# SKC_PSU.net
KiCad netlist of a schematic drawn in Altium Designer
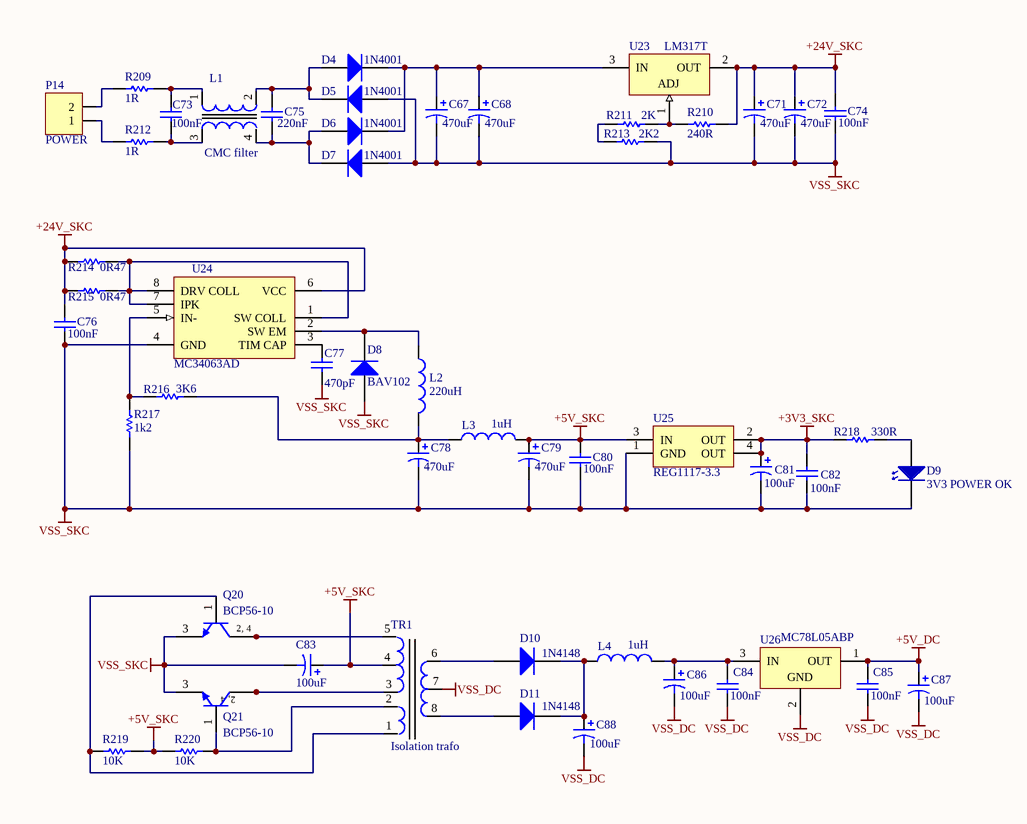
[diagram p0: SKC_PSU.SchDoc]

(export (version "E")
  (design (tool "Eeschema 10.0.6"))
  (components
    (comp (ref "C67")
      (value "470uF")
      (footprint "CAPPR5-10X16")
      (description "Aluminum Electrolytic Capacitor, Radial Style with Long Leads: 470uF, 35V")
      (fields (field (name "PUBLISHER") "Altium Limited"))
      (libsource (lib "Vishay Roederstein Electrolytic Radial-Lead Capacitor") (part "EKA00DD347F00"))
    )
    (comp (ref "C68")
      (value "470uF")
      (footprint "CAPPR5-10X16")
      (description "Aluminum Electrolytic Capacitor, Radial Style with Long Leads: 470uF, 35V")
      (fields (field (name "PUBLISHER") "Altium Limited"))
      (libsource (lib "Vishay Roederstein Electrolytic Radial-Lead Capacitor") (part "EKA00DD347F00"))
    )
    (comp (ref "C71")
      (value "470uF")
      (footprint "CAPPR5-10X16")
      (description "Aluminum Electrolytic Capacitor, Radial Style with Long Leads: 470uF, 35V")
      (fields (field (name "PUBLISHER") "Altium Limited"))
      (libsource (lib "Vishay Roederstein Electrolytic Radial-Lead Capacitor") (part "EKA00DD347F00"))
    )
    (comp (ref "C72")
      (value "470uF")
      (footprint "CAPPR5-10X16")
      (description "Aluminum Electrolytic Capacitor, Radial Style with Long Leads: 470uF, 35V")
      (fields (field (name "PUBLISHER") "Altium Limited"))
      (libsource (lib "Vishay Roederstein Electrolytic Radial-Lead Capacitor") (part "EKA00DD347F00"))
    )
    (comp (ref "C73")
      (value "100nF")
      (footprint "VP60-3.6")
      (description "Dipped Radial Multilayer Ceramic Capacitor COG (NPO): 68nF, 50/63V")
      (fields (field (name "PUBLISHER") "Altium Limited"))
      (libsource (lib "Vishay Vitramon Ceramic Dipped Capacitor") (part "VP60BA683KA"))
    )
    (comp (ref "C74")
      (value "100nF")
      (footprint "1206")
      (description "Ceramic Chip Capacitor - Standard")
      (fields (field (name "PUBLISHER") "Altium Limited"))
      (libsource (lib "KEMET Chip Capacitor") (part "C1206"))
    )
    (comp (ref "C75")
      (value "220nF")
      (footprint "VP60-3.6")
      (description "Dipped Radial Multilayer Ceramic Capacitor COG (NPO): 68nF, 50/63V")
      (fields (field (name "PUBLISHER") "Altium Limited"))
      (libsource (lib "Vishay Vitramon Ceramic Dipped Capacitor") (part "VP60BA683KA"))
    )
    (comp (ref "C76")
      (value "100nF")
      (footprint "1206")
      (description "Ceramic Chip Capacitor - Standard")
      (fields (field (name "PUBLISHER") "Altium Limited"))
      (libsource (lib "KEMET Chip Capacitor") (part "C1206"))
    )
    (comp (ref "C77")
      (value "470pF")
      (footprint "0805")
      (description "Ceramic Chip Capacitor - Standard")
      (fields (field (name "PUBLISHER") "Altium Limited"))
      (libsource (lib "KEMET Chip Capacitor") (part "C0805"))
    )
    (comp (ref "C78")
      (value "470uF")
      (footprint "CAPPR5-10X16")
      (description "Aluminum Electrolytic Capacitor, Radial Style with Long Leads: 470uF, 35V")
      (fields (field (name "PUBLISHER") "Altium Limited"))
      (libsource (lib "Vishay Roederstein Electrolytic Radial-Lead Capacitor") (part "EKA00DD347F00"))
    )
    (comp (ref "C79")
      (value "470uF")
      (footprint "CAPPR5-10X16")
      (description "Aluminum Electrolytic Capacitor, Radial Style with Long Leads: 470uF, 35V")
      (fields (field (name "PUBLISHER") "Altium Limited"))
      (libsource (lib "Vishay Roederstein Electrolytic Radial-Lead Capacitor") (part "EKA00DD347F00"))
    )
    (comp (ref "C80")
      (value "100nF")
      (footprint "1206")
      (description "Ceramic Chip Capacitor - Standard")
      (fields (field (name "PUBLISHER") "Altium Limited"))
      (libsource (lib "KEMET Chip Capacitor") (part "C1206"))
    )
    (comp (ref "C81")
      (value "100uF")
      (footprint "CAPPR2-5X11")
      (description "Aluminum Electrolytic Capacitor, Radial Style with Long Leads: 100uF, 16V")
      (fields (field (name "PUBLISHER") "Altium Limited"))
      (libsource (lib "Vishay Roederstein Electrolytic Radial-Lead Capacitor") (part "EKA00AA310D00"))
    )
    (comp (ref "C82")
      (value "100nF")
      (footprint "1206")
      (description "Ceramic Chip Capacitor - Standard")
      (fields (field (name "PUBLISHER") "Altium Limited"))
      (libsource (lib "KEMET Chip Capacitor") (part "C1206"))
    )
    (comp (ref "C83")
      (value "100uF")
      (footprint "CAPPR2-5X11")
      (description "Aluminum Electrolytic Capacitor, Radial Style with Long Leads: 100uF, 16V")
      (fields (field (name "PUBLISHER") "Altium Limited"))
      (libsource (lib "Vishay Roederstein Electrolytic Radial-Lead Capacitor") (part "EKA00AA310D00"))
    )
    (comp (ref "C84")
      (value "100nF")
      (footprint "1206")
      (description "Ceramic Chip Capacitor - Standard")
      (fields (field (name "PUBLISHER") "Altium Limited"))
      (libsource (lib "KEMET Chip Capacitor") (part "C1206"))
    )
    (comp (ref "C85")
      (value "100nF")
      (footprint "1206")
      (description "Ceramic Chip Capacitor - Standard")
      (fields (field (name "PUBLISHER") "Altium Limited"))
      (libsource (lib "KEMET Chip Capacitor") (part "C1206"))
    )
    (comp (ref "C86")
      (value "100uF")
      (footprint "CAPPR2-5X11")
      (description "Aluminum Electrolytic Capacitor, Radial Style with Long Leads: 100uF, 16V")
      (fields (field (name "PUBLISHER") "Altium Limited"))
      (libsource (lib "Vishay Roederstein Electrolytic Radial-Lead Capacitor") (part "EKA00AA310D00"))
    )
    (comp (ref "C87")
      (value "100uF")
      (footprint "CAPPR2-5X11")
      (description "Aluminum Electrolytic Capacitor, Radial Style with Long Leads: 100uF, 16V")
      (fields (field (name "PUBLISHER") "Altium Limited"))
      (libsource (lib "Vishay Roederstein Electrolytic Radial-Lead Capacitor") (part "EKA00AA310D00"))
    )
    (comp (ref "C88")
      (value "100uF")
      (footprint "CAPPR2-5X11")
      (description "Aluminum Electrolytic Capacitor, Radial Style with Long Leads: 100uF, 16V")
      (fields (field (name "PUBLISHER") "Altium Limited"))
      (libsource (lib "Vishay Roederstein Electrolytic Radial-Lead Capacitor") (part "EKA00AA310D00"))
    )
    (comp (ref "D4")
      (value "1N4001")
      (footprint "DO-41")
      (description "1 Amp General Purpose Rectifier")
      (fields (field (name "PUBLISHER") "Altium Limited"))
      (libsource (lib "Miscellaneous Devices") (part "Diode 1N4007"))
    )
    (comp (ref "D5")
      (value "1N4001")
      (footprint "DO-41")
      (description "1 Amp General Purpose Rectifier")
      (fields (field (name "PUBLISHER") "Altium Limited"))
      (libsource (lib "Miscellaneous Devices") (part "Diode 1N4007"))
    )
    (comp (ref "D6")
      (value "1N4001")
      (footprint "DO-41")
      (description "1 Amp General Purpose Rectifier")
      (fields (field (name "PUBLISHER") "Altium Limited"))
      (libsource (lib "Miscellaneous Devices") (part "Diode 1N4007"))
    )
    (comp (ref "D7")
      (value "1N4001")
      (footprint "DO-41")
      (description "1 Amp General Purpose Rectifier")
      (fields (field (name "PUBLISHER") "Altium Limited"))
      (libsource (lib "Miscellaneous Devices") (part "Diode 1N4007"))
    )
    (comp (ref "D8")
      (value "BAV102")
      (footprint "SOD80C")
      (description "General-purpose Diode")
      (fields (field (name "PUBLISHER") "Altium Limited"))
      (libsource (lib "Philips Discrete Diode - Switching") (part "BAV102"))
    )
    (comp (ref "D9")
      (value "3V3 POWER OK")
      (footprint "LED 3mm")
      (libsource (lib "ProjectLibrary") (part "LED 3mm"))
    )
    (comp (ref "D10")
      (value "1N4148")
      (footprint "DO-35")
      (description "High Conductance Fast Diode")
      (fields (field (name "PUBLISHER") "Altium Limited"))
      (libsource (lib "Miscellaneous Devices") (part "Diode 1N4148"))
    )
    (comp (ref "D11")
      (value "1N4148")
      (footprint "DO-35")
      (description "High Conductance Fast Diode")
      (fields (field (name "PUBLISHER") "Altium Limited"))
      (libsource (lib "Miscellaneous Devices") (part "Diode 1N4148"))
    )
    (comp (ref "L1")
      (value "CMC filter")
      (footprint "MREZNI FILTER")
      (libsource (lib "ProjectLibrary") (part "MREZNI FILTER"))
    )
    (comp (ref "L2")
      (value "220uH")
      (footprint "Miscellaneous Devices:RB5-10.5")
      (description "SMT Power Choke Coil; Size 7.3×6.6×3.0mm, ±20% Tolerance, 0.82uH, 13A")
      (fields (field (name "PUBLISHER") "Altium Limited"))
      (libsource (lib "SSM Inductor") (part "PCMC063T-R82MN"))
    )
    (comp (ref "L3")
      (value "1uH")
      (footprint "Miscellaneous Devices:RB5-10.5")
      (description "SMT Power Choke Coil; Size 7.3×6.6×3.0mm, ±20% Tolerance, 0.82uH, 13A")
      (fields (field (name "PUBLISHER") "Altium Limited"))
      (libsource (lib "SSM Inductor") (part "PCMC063T-R82MN"))
    )
    (comp (ref "L4")
      (value "1uH")
      (footprint "Miscellaneous Devices:RB5-10.5")
      (description "SMT Power Choke Coil; Size 7.3×6.6×3.0mm, ±20% Tolerance, 0.82uH, 13A")
      (fields (field (name "PUBLISHER") "Altium Limited"))
      (libsource (lib "SSM Inductor") (part "PCMC063T-R82MN"))
    )
    (comp (ref "P14")
      (value "POWER")
      (footprint "TERMINAL BLOK 2")
      (description "Terminal blok konektor 3,5 mm")
      (libsource (lib "ProjectLibrary") (part "TERMINAL BLOK 2"))
    )
    (comp (ref "Q20")
      (value "BCP56-10")
      (footprint "SOT223_N")
      (description "NPN Medium Power Transistor")
      (fields (field (name "PUBLISHER") "Altium Limited"))
      (libsource (lib "Philips Discrete BJT - Medium Power") (part "BCP56-10"))
    )
    (comp (ref "Q21")
      (value "BCP56-10")
      (footprint "SOT223_N")
      (description "NPN Medium Power Transistor")
      (fields (field (name "PUBLISHER") "Altium Limited"))
      (libsource (lib "Philips Discrete BJT - Medium Power") (part "BCP56-10"))
    )
    (comp (ref "R209")
      (value "1R")
      (footprint "R6.35x2.3")
      (description "Metal Oxide Film Resistor, 0.1 Ohm to 47k Ohm Range, 2% and 5% Tolerance, 0.5 W")
      (fields (field (name "PUBLISHER") "Altium Limited"))
      (libsource (lib "Panasonic Resistor") (part "ERG12"))
    )
    (comp (ref "R210")
      (value "240R")
      (footprint "ERA-0805")
      (fields (field (name "PUBLISHER") "Altium Limited"))
      (libsource (lib "Panasonic Resistor") (part "ERAS"))
    )
    (comp (ref "R211")
      (value "2K")
      (footprint "ERA-0805")
      (fields (field (name "PUBLISHER") "Altium Limited"))
      (libsource (lib "Panasonic Resistor") (part "ERAS"))
    )
    (comp (ref "R212")
      (value "1R")
      (footprint "R6.35x2.3")
      (description "Metal Oxide Film Resistor, 0.1 Ohm to 47k Ohm Range, 2% and 5% Tolerance, 0.5 W")
      (fields (field (name "PUBLISHER") "Altium Limited"))
      (libsource (lib "Panasonic Resistor") (part "ERG12"))
    )
    (comp (ref "R213")
      (value "2K2")
      (footprint "ERA-0805")
      (fields (field (name "PUBLISHER") "Altium Limited"))
      (libsource (lib "Panasonic Resistor") (part "ERAS"))
    )
    (comp (ref "R214")
      (value "0R47")
      (footprint "RD6.35x2.3")
      (description "Carbon Film Resistor, 1 Ohm to 3.3M Ohm Range, 5% Tolerance, 0.5 W")
      (fields (field (name "PUBLISHER") "Altium Limited"))
      (libsource (lib "Panasonic Resistor") (part "ERDS1T"))
    )
    (comp (ref "R215")
      (value "0R47")
      (footprint "RD6.35x2.3")
      (description "Carbon Film Resistor, 1 Ohm to 3.3M Ohm Range, 5% Tolerance, 0.5 W")
      (fields (field (name "PUBLISHER") "Altium Limited"))
      (libsource (lib "Panasonic Resistor") (part "ERDS1T"))
    )
    (comp (ref "R216")
      (value "3K6")
      (footprint "ERA-0805")
      (fields (field (name "PUBLISHER") "Altium Limited"))
      (libsource (lib "Panasonic Resistor") (part "ERAS"))
    )
    (comp (ref "R217")
      (value "1k2")
      (footprint "ERA-0805")
      (fields (field (name "PUBLISHER") "Altium Limited"))
      (libsource (lib "Panasonic Resistor") (part "ERAS"))
    )
    (comp (ref "R218")
      (value "330R")
      (footprint "ERA-0603")
      (fields (field (name "PUBLISHER") "Altium Limited"))
      (libsource (lib "Panasonic Resistor") (part "ERA3Y"))
    )
    (comp (ref "R219")
      (value "10K")
      (footprint "ERA-0805")
      (fields (field (name "PUBLISHER") "Altium Limited"))
      (libsource (lib "Panasonic Resistor") (part "ERAS"))
    )
    (comp (ref "R220")
      (value "10K")
      (footprint "ERA-0805")
      (fields (field (name "PUBLISHER") "Altium Limited"))
      (libsource (lib "Panasonic Resistor") (part "ERAS"))
    )
    (comp (ref "TR1")
      (value "Isolation trafo")
      (footprint "ISOLATION TRAFO 1")
      (description "SMPS small ferite toroide trafo")
      (libsource (lib "ProjectLibrary") (part "ISOLATION TRAFO 1"))
    )
    (comp (ref "U23")
      (value "LM317T")
      (footprint "221A-04")
      (description "3-Terminal Adjustable Positive Voltage Regulator")
      (fields (field (name "PUBLISHER") "Altium Limited"))
      (libsource (lib "Motorola Power Mgt Voltage Regulator") (part "LM317T"))
    )
    (comp (ref "U24")
      (value "MC34063AD")
      (footprint "ON Semi Power Mgt Supervisory Cct:626-05")
      (description "DC-to-DC Converter Control Circuit")
      (fields (field (name "PUBLISHER") "Altium Limited"))
      (libsource (lib "ON Semi Power Mgt DC-DC Converter") (part "MC34063AD"))
    )
    (comp (ref "U25")
      (value "REG1117-3.3")
      (footprint "ZZ311")
      (description "800mA and 1A Low Dropout Positive Regulator 2.85V, 3.3V, 5V, and Adjustable")
      (fields (field (name "PUBLISHER") "Altium Limited"))
      (libsource (lib "BB Power Mgt Voltage Regulator") (part "REG1117-3.3"))
    )
    (comp (ref "U26")
      (value "MC78L05ABP")
      (footprint "29-04")
      (description "3-Terminal Low-Current Positive Fixed Voltage Regulator")
      (fields (field (name "PUBLISHER") "Altium Limited"))
      (libsource (lib "Motorola Power Mgt Voltage Regulator") (part "MC78L05ABP"))
    )
  )
  (nets
    (net (code "1") (name "+3V3_SKC") (class "Default")
      (node (ref "C81") (pin "1") (pinfunction "1_1") (pintype "passive"))
      (node (ref "C82") (pin "2") (pinfunction "2_2") (pintype "passive"))
      (node (ref "R218") (pin "1") (pinfunction "1_1") (pintype "passive"))
      (node (ref "U25") (pin "2") (pinfunction "OUT_2") (pintype "power_in"))
      (node (ref "U25") (pin "4") (pinfunction "OUT_4") (pintype "power_in"))
    )
    (net (code "2") (name "+5V_DC") (class "Default")
      (node (ref "C85") (pin "2") (pinfunction "2_2") (pintype "passive"))
      (node (ref "C87") (pin "1") (pinfunction "1_1") (pintype "passive"))
      (node (ref "U26") (pin "1") (pinfunction "OUT_1") (pintype "power_in"))
    )
    (net (code "3") (name "+5V_SKC") (class "Default")
      (node (ref "C79") (pin "1") (pinfunction "1_1") (pintype "passive"))
      (node (ref "C80") (pin "2") (pinfunction "2_2") (pintype "passive"))
      (node (ref "C83") (pin "1") (pinfunction "1_1") (pintype "passive"))
      (node (ref "L3") (pin "2") (pinfunction "2_2") (pintype "passive"))
      (node (ref "R219") (pin "1") (pinfunction "1_1") (pintype "passive"))
      (node (ref "R220") (pin "2") (pinfunction "2_2") (pintype "passive"))
      (node (ref "TR1") (pin "4") (pinfunction "4_4") (pintype "passive"))
      (node (ref "U25") (pin "3") (pinfunction "IN_3") (pintype "power_in"))
    )
    (net (code "4") (name "+24V_SKC") (class "Default")
      (node (ref "C71") (pin "1") (pinfunction "1_1") (pintype "passive"))
      (node (ref "C72") (pin "1") (pinfunction "1_1") (pintype "passive"))
      (node (ref "C74") (pin "2") (pinfunction "2_2") (pintype "passive"))
      (node (ref "C76") (pin "2") (pinfunction "2_2") (pintype "passive"))
      (node (ref "R210") (pin "1") (pinfunction "1_1") (pintype "passive"))
      (node (ref "R214") (pin "1") (pinfunction "1_1") (pintype "passive"))
      (node (ref "R215") (pin "1") (pinfunction "1_1") (pintype "passive"))
      (node (ref "U23") (pin "2") (pinfunction "OUT_2") (pintype "power_in"))
      (node (ref "U24") (pin "6") (pinfunction "VCC_6") (pintype "power_in"))
    )
    (net (code "5") (name "Net-(C73-Pad1)") (class "Default")
      (node (ref "C73") (pin "1") (pinfunction "1_1") (pintype "passive"))
      (node (ref "L1") (pin "3") (pintype "passive"))
      (node (ref "R212") (pin "1") (pinfunction "1_1") (pintype "passive"))
    )
    (net (code "6") (name "Net-(C73-Pad2)") (class "Default")
      (node (ref "C73") (pin "2") (pinfunction "2_2") (pintype "passive"))
      (node (ref "L1") (pin "1") (pintype "passive"))
      (node (ref "R209") (pin "1") (pinfunction "1_1") (pintype "passive"))
    )
    (net (code "7") (name "Net-(C78-Pad1)") (class "Default")
      (node (ref "C78") (pin "1") (pinfunction "1_1") (pintype "passive"))
      (node (ref "L2") (pin "2") (pinfunction "2_2") (pintype "passive"))
      (node (ref "L3") (pin "1") (pinfunction "1_1") (pintype "passive"))
      (node (ref "R216") (pin "2") (pinfunction "2_2") (pintype "passive"))
    )
    (net (code "8") (name "Net-(D4-A)") (class "Default")
      (node (ref "C75") (pin "2") (pinfunction "2_2") (pintype "passive"))
      (node (ref "D4") (pin "1") (pinfunction "A_1") (pintype "passive"))
      (node (ref "D5") (pin "2") (pinfunction "K_2") (pintype "passive"))
      (node (ref "L1") (pin "2") (pintype "passive"))
    )
    (net (code "9") (name "Net-(D4-K)") (class "Default")
      (node (ref "C67") (pin "1") (pinfunction "1_1") (pintype "passive"))
      (node (ref "C68") (pin "1") (pinfunction "1_1") (pintype "passive"))
      (node (ref "D4") (pin "2") (pinfunction "K_2") (pintype "passive"))
      (node (ref "D6") (pin "2") (pinfunction "K_2") (pintype "passive"))
      (node (ref "U23") (pin "3") (pinfunction "IN_3") (pintype "power_in"))
    )
    (net (code "10") (name "Net-(D6-A)") (class "Default")
      (node (ref "C75") (pin "1") (pinfunction "1_1") (pintype "passive"))
      (node (ref "D6") (pin "1") (pinfunction "A_1") (pintype "passive"))
      (node (ref "D7") (pin "2") (pinfunction "K_2") (pintype "passive"))
      (node (ref "L1") (pin "4") (pintype "passive"))
    )
    (net (code "11") (name "Net-(D8-K)") (class "Default")
      (node (ref "D8") (pin "2") (pinfunction "K_2") (pintype "passive"))
      (node (ref "L2") (pin "1") (pinfunction "1_1") (pintype "passive"))
      (node (ref "U24") (pin "2") (pinfunction "SW_EM_2") (pintype "passive"))
    )
    (net (code "12") (name "Net-(D9-Pad2)") (class "Default")
      (node (ref "D9") (pin "2") (pinfunction "2_2") (pintype "passive"))
      (node (ref "R218") (pin "2") (pinfunction "2_2") (pintype "passive"))
    )
    (net (code "13") (name "Net-(D10-A)") (class "Default")
      (node (ref "D10") (pin "1") (pinfunction "A_1") (pintype "passive"))
      (node (ref "TR1") (pin "6") (pinfunction "6_6") (pintype "passive"))
    )
    (net (code "14") (name "Net-(D10-K)") (class "Default")
      (node (ref "C88") (pin "1") (pinfunction "1_1") (pintype "passive"))
      (node (ref "D10") (pin "2") (pinfunction "K_2") (pintype "passive"))
      (node (ref "D11") (pin "2") (pinfunction "K_2") (pintype "passive"))
      (node (ref "L4") (pin "1") (pinfunction "1_1") (pintype "passive"))
    )
    (net (code "15") (name "Net-(D11-A)") (class "Default")
      (node (ref "D11") (pin "1") (pinfunction "A_1") (pintype "passive"))
      (node (ref "TR1") (pin "8") (pinfunction "8_8") (pintype "passive"))
    )
    (net (code "16") (name "Net-(P14-Pad1)") (class "Default")
      (node (ref "P14") (pin "1") (pinfunction "1_1") (pintype "passive"))
      (node (ref "R212") (pin "2") (pinfunction "2_2") (pintype "passive"))
    )
    (net (code "17") (name "Net-(P14-Pad2)") (class "Default")
      (node (ref "P14") (pin "2") (pinfunction "2_2") (pintype "passive"))
      (node (ref "R209") (pin "2") (pinfunction "2_2") (pintype "passive"))
    )
    (net (code "18") (name "Net-(Q20-B)") (class "Default")
      (node (ref "Q20") (pin "1") (pinfunction "B_1") (pintype "passive"))
      (node (ref "R219") (pin "2") (pinfunction "2_2") (pintype "passive"))
      (node (ref "TR1") (pin "1") (pinfunction "1_1") (pintype "passive"))
    )
    (net (code "19") (name "Net-(Q20-C-Pad2)") (class "Default")
      (node (ref "Q20") (pin "2") (pinfunction "C_2") (pintype "passive"))
      (node (ref "Q20") (pin "4") (pinfunction "C_4") (pintype "passive"))
      (node (ref "TR1") (pin "5") (pinfunction "5_5") (pintype "passive"))
    )
    (net (code "20") (name "Net-(Q21-B)") (class "Default")
      (node (ref "Q21") (pin "1") (pinfunction "B_1") (pintype "passive"))
      (node (ref "R220") (pin "1") (pinfunction "1_1") (pintype "passive"))
      (node (ref "TR1") (pin "2") (pinfunction "2_2") (pintype "passive"))
    )
    (net (code "21") (name "Net-(Q21-C-Pad2)") (class "Default")
      (node (ref "Q21") (pin "2") (pinfunction "C_2") (pintype "passive"))
      (node (ref "Q21") (pin "4") (pinfunction "C_4") (pintype "passive"))
      (node (ref "TR1") (pin "3") (pinfunction "3_3") (pintype "passive"))
    )
    (net (code "22") (name "Net-(R211-Pad1)") (class "Default")
      (node (ref "R211") (pin "1") (pinfunction "1_1") (pintype "passive"))
      (node (ref "R213") (pin "2") (pinfunction "2_2") (pintype "passive"))
    )
    (net (code "23") (name "Net-(U23-ADJ)") (class "Default")
      (node (ref "R210") (pin "2") (pinfunction "2_2") (pintype "passive"))
      (node (ref "R211") (pin "2") (pinfunction "2_2") (pintype "passive"))
      (node (ref "U23") (pin "1") (pinfunction "ADJ_1") (pintype "input"))
    )
    (net (code "24") (name "Net-(U24-DRV_COLL)") (class "Default")
      (node (ref "R214") (pin "2") (pinfunction "2_2") (pintype "passive"))
      (node (ref "R215") (pin "2") (pinfunction "2_2") (pintype "passive"))
      (node (ref "U24") (pin "1") (pinfunction "SW_COLL_1") (pintype "passive"))
      (node (ref "U24") (pin "7") (pinfunction "IPK_7") (pintype "passive"))
      (node (ref "U24") (pin "8") (pinfunction "DRV_COLL_8") (pintype "open_collector"))
    )
    (net (code "25") (name "Net-(U24-IN-)") (class "Default")
      (node (ref "R216") (pin "1") (pinfunction "1_1") (pintype "passive"))
      (node (ref "R217") (pin "2") (pinfunction "2_2") (pintype "passive"))
      (node (ref "U24") (pin "5") (pinfunction "IN-_5") (pintype "input"))
    )
    (net (code "26") (name "Net-(U24-TIM_CAP)") (class "Default")
      (node (ref "C77") (pin "2") (pinfunction "2_2") (pintype "passive"))
      (node (ref "U24") (pin "3") (pinfunction "TIM_CAP_3") (pintype "passive"))
    )
    (net (code "27") (name "Net-(U26-IN)") (class "Default")
      (node (ref "C84") (pin "2") (pinfunction "2_2") (pintype "passive"))
      (node (ref "C86") (pin "1") (pinfunction "1_1") (pintype "passive"))
      (node (ref "L4") (pin "2") (pinfunction "2_2") (pintype "passive"))
      (node (ref "U26") (pin "3") (pinfunction "IN_3") (pintype "power_in"))
    )
    (net (code "28") (name "VSS_DC") (class "Default")
      (node (ref "C84") (pin "1") (pinfunction "1_1") (pintype "passive"))
      (node (ref "C85") (pin "1") (pinfunction "1_1") (pintype "passive"))
      (node (ref "C86") (pin "2") (pinfunction "2_2") (pintype "passive"))
      (node (ref "C87") (pin "2") (pinfunction "2_2") (pintype "passive"))
      (node (ref "C88") (pin "2") (pinfunction "2_2") (pintype "passive"))
      (node (ref "TR1") (pin "7") (pinfunction "7_7") (pintype "passive"))
      (node (ref "U26") (pin "2") (pinfunction "GND_2") (pintype "power_in"))
    )
    (net (code "29") (name "VSS_SKC") (class "Default")
      (node (ref "C67") (pin "2") (pinfunction "2_2") (pintype "passive"))
      (node (ref "C68") (pin "2") (pinfunction "2_2") (pintype "passive"))
      (node (ref "C71") (pin "2") (pinfunction "2_2") (pintype "passive"))
      (node (ref "C72") (pin "2") (pinfunction "2_2") (pintype "passive"))
      (node (ref "C74") (pin "1") (pinfunction "1_1") (pintype "passive"))
      (node (ref "C76") (pin "1") (pinfunction "1_1") (pintype "passive"))
      (node (ref "C77") (pin "1") (pinfunction "1_1") (pintype "passive"))
      (node (ref "C78") (pin "2") (pinfunction "2_2") (pintype "passive"))
      (node (ref "C79") (pin "2") (pinfunction "2_2") (pintype "passive"))
      (node (ref "C80") (pin "1") (pinfunction "1_1") (pintype "passive"))
      (node (ref "C81") (pin "2") (pinfunction "2_2") (pintype "passive"))
      (node (ref "C82") (pin "1") (pinfunction "1_1") (pintype "passive"))
      (node (ref "C83") (pin "2") (pinfunction "2_2") (pintype "passive"))
      (node (ref "D5") (pin "1") (pinfunction "A_1") (pintype "passive"))
      (node (ref "D7") (pin "1") (pinfunction "A_1") (pintype "passive"))
      (node (ref "D8") (pin "1") (pinfunction "A_1") (pintype "passive"))
      (node (ref "D9") (pin "1") (pinfunction "1_1") (pintype "passive"))
      (node (ref "Q20") (pin "3") (pinfunction "E_3") (pintype "passive"))
      (node (ref "Q21") (pin "3") (pinfunction "E_3") (pintype "passive"))
      (node (ref "R213") (pin "1") (pinfunction "1_1") (pintype "passive"))
      (node (ref "R217") (pin "1") (pinfunction "1_1") (pintype "passive"))
      (node (ref "U24") (pin "4") (pinfunction "GND_4") (pintype "power_in"))
      (node (ref "U25") (pin "1") (pinfunction "GND_1") (pintype "power_in"))
    )
  )
)
